# current_amplifier_01.net
KiCad netlist of a schematic drawn in Altium Designer
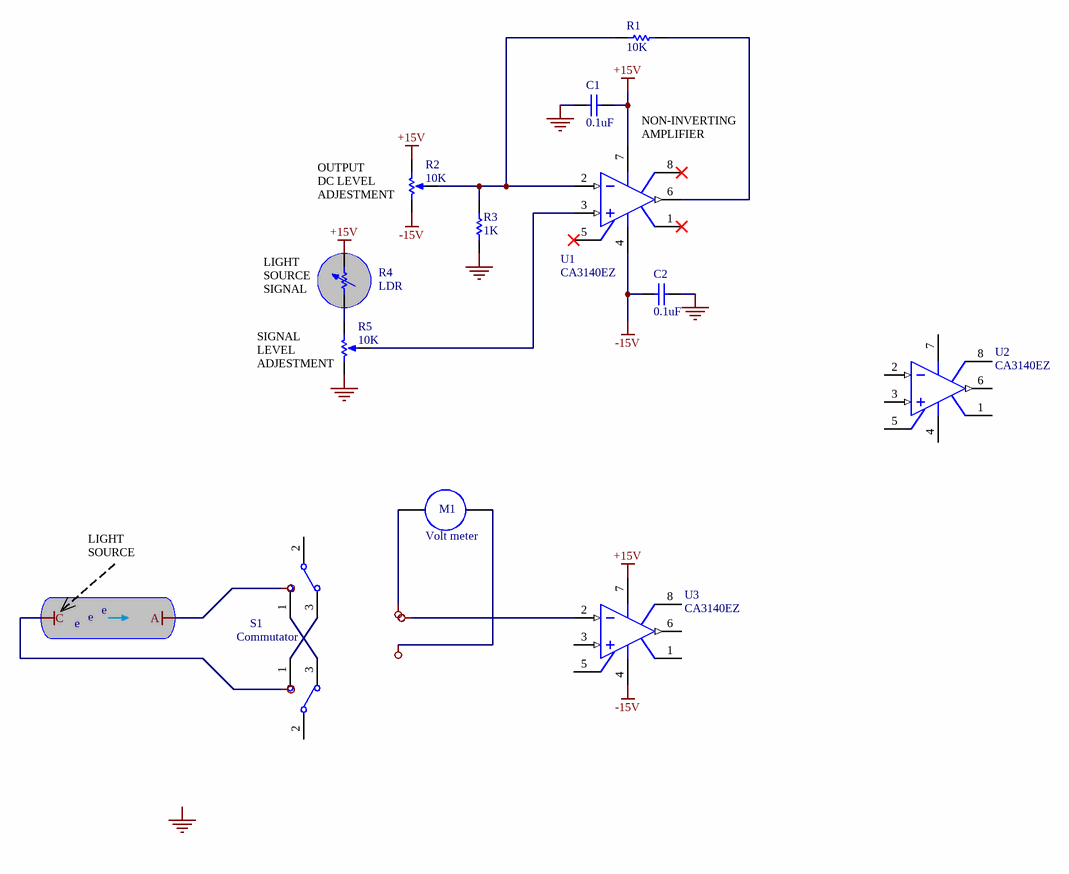
[diagram p0: current amplifier 01.SchDoc]

(export (version "E")
  (design (tool "Eeschema 10.0.6"))
  (components
    (comp (ref "C1")
      (value "0.1uF")
      (footprint "RAD-0.3")
      (description "Capacitor")
      (fields (field (name "PUBLISHER") "Altium Limited"))
      (libsource (lib "Miscellaneous Devices") (part "Cap"))
    )
    (comp (ref "C2")
      (value "0.1uF")
      (footprint "RAD-0.3")
      (description "Capacitor")
      (fields (field (name "PUBLISHER") "Altium Limited"))
      (libsource (lib "Miscellaneous Devices") (part "Cap"))
    )
    (comp (ref "M1")
      (value "Volt meter")
      (footprint "RAD-0.1")
      (description "Indicating Instrument")
      (fields (field (name "PUBLISHER") "Altium Limited"))
      (libsource (lib "Miscellaneous Devices") (part "Meter"))
    )
    (comp (ref "R1")
      (value "10K")
      (footprint "AXIAL-0.3")
      (description "Resistor")
      (fields (field (name "PUBLISHER") "Altium Limited"))
      (libsource (lib "Miscellaneous Devices") (part "Res1"))
    )
    (comp (ref "R2")
      (value "10K")
      (footprint "VR5")
      (description "Potentiometer")
      (fields (field (name "PUBLISHER") "Altium Limited"))
      (libsource (lib "Miscellaneous Devices") (part "RPot"))
    )
    (comp (ref "R3")
      (value "1K")
      (footprint "AXIAL-0.3")
      (description "Resistor")
      (fields (field (name "PUBLISHER") "Altium Limited"))
      (libsource (lib "Miscellaneous Devices") (part "Res1"))
    )
    (comp (ref "R4")
      (value "LDR")
      (footprint "AXIAL-0.7")
      (description "Variable Resistor")
      (fields (field (name "PUBLISHER") "Altium Limited"))
      (libsource (lib "Miscellaneous Devices") (part "Res Adj1"))
    )
    (comp (ref "R5")
      (value "10K")
      (footprint "VR5")
      (description "Potentiometer")
      (fields (field (name "PUBLISHER") "Altium Limited"))
      (libsource (lib "Miscellaneous Devices") (part "RPot"))
    )
    (comp (ref "S1")
      (value "Commutator")
      (footprint "TL36WW15050")
      (description "SPDT Subminiature Toggle Switch, Right Angle Mounting, Vertical Actuation")
      (fields (field (name "PUBLISHER") "Altium Limited"))
      (libsource (lib "Miscellaneous Devices") (part "SW-SPDT"))
    )
    (comp (ref "S2")
      (value "SW-SPDT")
      (footprint "TL36WW15050")
      (description "SPDT Subminiature Toggle Switch, Right Angle Mounting, Vertical Actuation")
      (fields (field (name "PUBLISHER") "Altium Limited"))
      (libsource (lib "Miscellaneous Devices") (part "SW-SPDT"))
    )
    (comp (ref "U1")
      (value "CA3140EZ")
      (footprint "H-08A")
      (description "FET Operational Amplifier")
      (fields (field (name "PUBLISHER") "Altium Limited"))
      (libsource (lib "Miscellaneous Devices") (part "Op Amp"))
    )
    (comp (ref "U2")
      (value "CA3140EZ")
      (footprint "H-08A")
      (description "FET Operational Amplifier")
      (fields (field (name "PUBLISHER") "Altium Limited"))
      (libsource (lib "Miscellaneous Devices") (part "Op Amp"))
    )
    (comp (ref "U3")
      (value "CA3140EZ")
      (footprint "H-08A")
      (description "FET Operational Amplifier")
      (fields (field (name "PUBLISHER") "Altium Limited"))
      (libsource (lib "Miscellaneous Devices") (part "Op Amp"))
    )
  )
  (nets
    (net (code "1") (name "+15V") (class "Default")
      (node (ref "C1") (pin "2") (pinfunction "2_2") (pintype "passive"))
      (node (ref "R2") (pin "1") (pinfunction "TOP_1") (pintype "passive"))
      (node (ref "R4") (pin "2") (pinfunction "2_2") (pintype "passive"))
      (node (ref "U1") (pin "7") (pinfunction "V+_7") (pintype "power_in"))
      (node (ref "U3") (pin "7") (pinfunction "V+_7") (pintype "power_in"))
    )
    (net (code "2") (name "-15V") (class "Default")
      (node (ref "C2") (pin "1") (pinfunction "1_1") (pintype "passive"))
      (node (ref "R2") (pin "2") (pinfunction "BOT_2") (pintype "passive"))
      (node (ref "U1") (pin "4") (pinfunction "V-_4") (pintype "power_in"))
      (node (ref "U3") (pin "4") (pinfunction "V-_4") (pintype "power_in"))
    )
    (net (code "4") (name "GND") (class "Default")
      (node (ref "C1") (pin "1") (pinfunction "1_1") (pintype "passive"))
      (node (ref "C2") (pin "2") (pinfunction "2_2") (pintype "passive"))
      (node (ref "R3") (pin "1") (pinfunction "1_1") (pintype "passive"))
      (node (ref "R5") (pin "2") (pinfunction "BOT_2") (pintype "passive"))
    )
    (net (code "5") (name "Net-(R2-TAP)") (class "Default")
      (node (ref "R1") (pin "1") (pinfunction "1_1") (pintype "passive"))
      (node (ref "R2") (pin "3") (pinfunction "TAP_3") (pintype "passive"))
      (node (ref "R3") (pin "2") (pinfunction "2_2") (pintype "passive"))
      (node (ref "U1") (pin "2") (pinfunction "IN-_2") (pintype "input"))
    )
    (net (code "6") (name "Net-(R5-TAP)") (class "Default")
      (node (ref "R5") (pin "3") (pinfunction "TAP_3") (pintype "passive"))
      (node (ref "U1") (pin "3") (pinfunction "IN+_3") (pintype "input"))
    )
    (net (code "7") (name "Net-(R5-TOP)") (class "Default")
      (node (ref "R4") (pin "1") (pinfunction "1_1") (pintype "passive"))
      (node (ref "R5") (pin "1") (pinfunction "TOP_1") (pintype "passive"))
    )
    (net (code "8") (name "Net-(S1-Pad1)") (class "Default")
      (node (ref "S1") (pin "1") (pinfunction "1_1") (pintype "passive"))
      (node (ref "S2") (pin "3") (pinfunction "3_3") (pintype "passive"))
    )
    (net (code "9") (name "Net-(S1-Pad3)") (class "Default")
      (node (ref "S1") (pin "3") (pinfunction "3_3") (pintype "passive"))
      (node (ref "S2") (pin "1") (pinfunction "1_1") (pintype "passive"))
    )
    (net (code "10") (name "Net-(U1-OUT)") (class "Default")
      (node (ref "R1") (pin "2") (pinfunction "2_2") (pintype "passive"))
      (node (ref "U1") (pin "6") (pinfunction "OUT_6") (pintype "output"))
    )
    (net (code "11") (name "VCC") (class "Default")
      (node (ref "M1") (pin "1") (pinfunction "1_1") (pintype "passive"))
      (node (ref "M1") (pin "2") (pinfunction "2_2") (pintype "passive"))
      (node (ref "U3") (pin "2") (pinfunction "IN-_2") (pintype "input"))
    )
    (net (code "12") (name "unconnected-(S1-Pad2)") (class "Default")
      (node (ref "S1") (pin "2") (pinfunction "2_2") (pintype "passive"))
    )
    (net (code "13") (name "unconnected-(S2-Pad2)") (class "Default")
      (node (ref "S2") (pin "2") (pinfunction "2_2") (pintype "passive"))
    )
    (net (code "14") (name "unconnected-(U1-OS_NUL-Pad1)") (class "Default")
      (node (ref "U1") (pin "1") (pinfunction "OS_NUL_1") (pintype "passive+no_connect"))
    )
    (net (code "15") (name "unconnected-(U1-OS_NUL-Pad5)") (class "Default")
      (node (ref "U1") (pin "5") (pinfunction "OS_NUL_5") (pintype "passive+no_connect"))
    )
    (net (code "16") (name "unconnected-(U1-TAB-Pad8)") (class "Default")
      (node (ref "U1") (pin "8") (pinfunction "TAB_8") (pintype "passive+no_connect"))
    )
    (net (code "17") (name "unconnected-(U2-IN+-Pad3)") (class "Default")
      (node (ref "U2") (pin "3") (pinfunction "IN+_3") (pintype "input"))
    )
    (net (code "18") (name "unconnected-(U2-IN--Pad2)") (class "Default")
      (node (ref "U2") (pin "2") (pinfunction "IN-_2") (pintype "input"))
    )
    (net (code "19") (name "unconnected-(U2-OS_NUL-Pad1)") (class "Default")
      (node (ref "U2") (pin "1") (pinfunction "OS_NUL_1") (pintype "passive"))
    )
    (net (code "20") (name "unconnected-(U2-OS_NUL-Pad5)") (class "Default")
      (node (ref "U2") (pin "5") (pinfunction "OS_NUL_5") (pintype "passive"))
    )
    (net (code "21") (name "unconnected-(U2-OUT-Pad6)") (class "Default")
      (node (ref "U2") (pin "6") (pinfunction "OUT_6") (pintype "output"))
    )
    (net (code "22") (name "unconnected-(U2-TAB-Pad8)") (class "Default")
      (node (ref "U2") (pin "8") (pinfunction "TAB_8") (pintype "passive"))
    )
    (net (code "23") (name "unconnected-(U2-V+-Pad7)") (class "Default")
      (node (ref "U2") (pin "7") (pinfunction "V+_7") (pintype "power_in"))
    )
    (net (code "24") (name "unconnected-(U2-V--Pad4)") (class "Default")
      (node (ref "U2") (pin "4") (pinfunction "V-_4") (pintype "power_in"))
    )
    (net (code "25") (name "unconnected-(U3-IN+-Pad3)") (class "Default")
      (node (ref "U3") (pin "3") (pinfunction "IN+_3") (pintype "input"))
    )
    (net (code "26") (name "unconnected-(U3-OS_NUL-Pad1)") (class "Default")
      (node (ref "U3") (pin "1") (pinfunction "OS_NUL_1") (pintype "passive"))
    )
    (net (code "27") (name "unconnected-(U3-OS_NUL-Pad5)") (class "Default")
      (node (ref "U3") (pin "5") (pinfunction "OS_NUL_5") (pintype "passive"))
    )
    (net (code "28") (name "unconnected-(U3-OUT-Pad6)") (class "Default")
      (node (ref "U3") (pin "6") (pinfunction "OUT_6") (pintype "output"))
    )
    (net (code "29") (name "unconnected-(U3-TAB-Pad8)") (class "Default")
      (node (ref "U3") (pin "8") (pinfunction "TAB_8") (pintype "passive"))
    )
  )
)
